# Telemetria_Comunica_o.net
KiCad netlist of a schematic drawn in Altium Designer
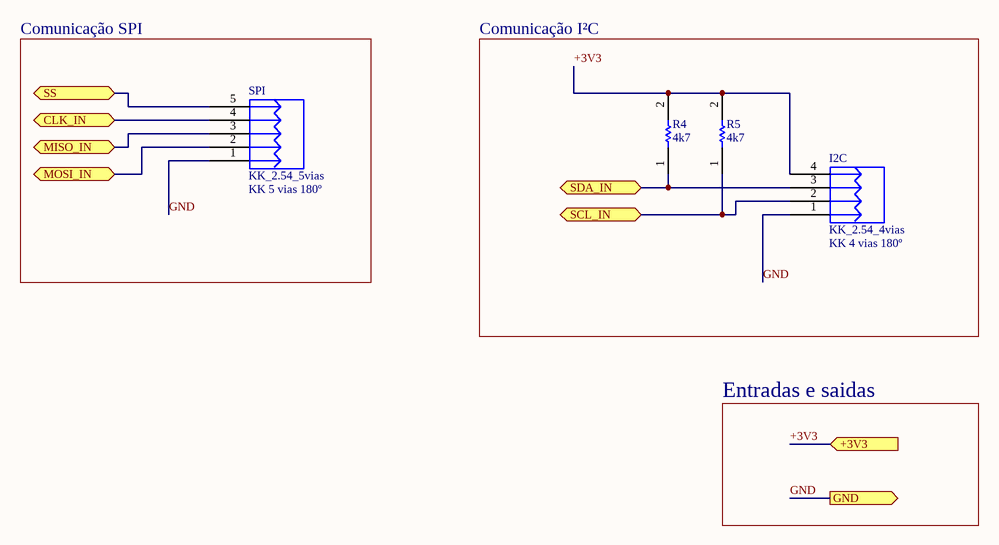
[diagram p0: Telemetria_Comunicação.SchDoc]

(export (version "E")
  (design (tool "Eeschema 10.0.6"))
  (components
    (comp (ref "I2C")
      (value "KK_2.54_4vias")
      (footprint "KK_4vias_180°")
      (description "Conector KK 2.54mm 4 vias")
      (fields (field (name "VALOR") "KK 4 vias 180º"))
      (libsource (lib "Sinaliza玢o_Official") (part "KK_2.54_4vias"))
    )
    (comp (ref "R4")
      (value "4k7")
      (footprint "RESC3216X60N")
      (description "Resistor")
      (fields
        (field (name "MANUFACTURER_PART_NUMBER") "CRCW12064K70FKEA")
        (field (name "MOUSER PART NUMBER") "71-CRCW1206-4.7K-E3")
      )
      (libsource (lib "Sinaliza玢o_Official") (part "Resistor 1206"))
    )
    (comp (ref "R5")
      (value "4k7")
      (footprint "RESC3216X60N")
      (description "Resistor")
      (fields
        (field (name "MANUFACTURER_PART_NUMBER") "CRCW12064K70FKEA")
        (field (name "MOUSER PART NUMBER") "71-CRCW1206-4.7K-E3")
      )
      (libsource (lib "Sinaliza玢o_Official") (part "Resistor 1206"))
    )
    (comp (ref "SPI")
      (value "KK_2.54_5vias")
      (footprint "KK_5vias_180°")
      (description "Conector KK 2.54mm 5 vias")
      (fields (field (name "VALOR") "KK 5 vias 180º"))
      (libsource (lib "Sinaliza玢o_Official") (part "KK_2.54_5vias"))
    )
  )
  (nets
    (net (code "1") (name "/+3V3") (class "Default")
      (node (ref "I2C") (pin "4") (pintype "passive"))
      (node (ref "R4") (pin "2") (pinfunction "2_2") (pintype "passive"))
      (node (ref "R5") (pin "2") (pinfunction "2_2") (pintype "passive"))
    )
    (net (code "2") (name "/CLK_IN") (class "Default") (node (ref "SPI") (pin "4") (pintype "passive")))
    (net (code "3") (name "/GND") (class "Default")
      (node (ref "I2C") (pin "1") (pintype "passive"))
      (node (ref "SPI") (pin "1") (pintype "passive"))
    )
    (net (code "4") (name "/MISO_IN") (class "Default") (node (ref "SPI") (pin "3") (pintype "passive")))
    (net (code "5") (name "/MOSI_IN") (class "Default") (node (ref "SPI") (pin "2") (pintype "passive")))
    (net (code "6") (name "/SCL_IN") (class "Default")
      (node (ref "I2C") (pin "2") (pintype "passive"))
      (node (ref "R5") (pin "1") (pinfunction "1_1") (pintype "passive"))
    )
    (net (code "7") (name "/SDA_IN") (class "Default")
      (node (ref "I2C") (pin "3") (pintype "passive"))
      (node (ref "R4") (pin "1") (pinfunction "1_1") (pintype "passive"))
    )
    (net (code "8") (name "/SS") (class "Default") (node (ref "SPI") (pin "5") (pintype "passive")))
  )
)
